# exp-4_sche.net
KiCad netlist of a schematic drawn in EAGLE
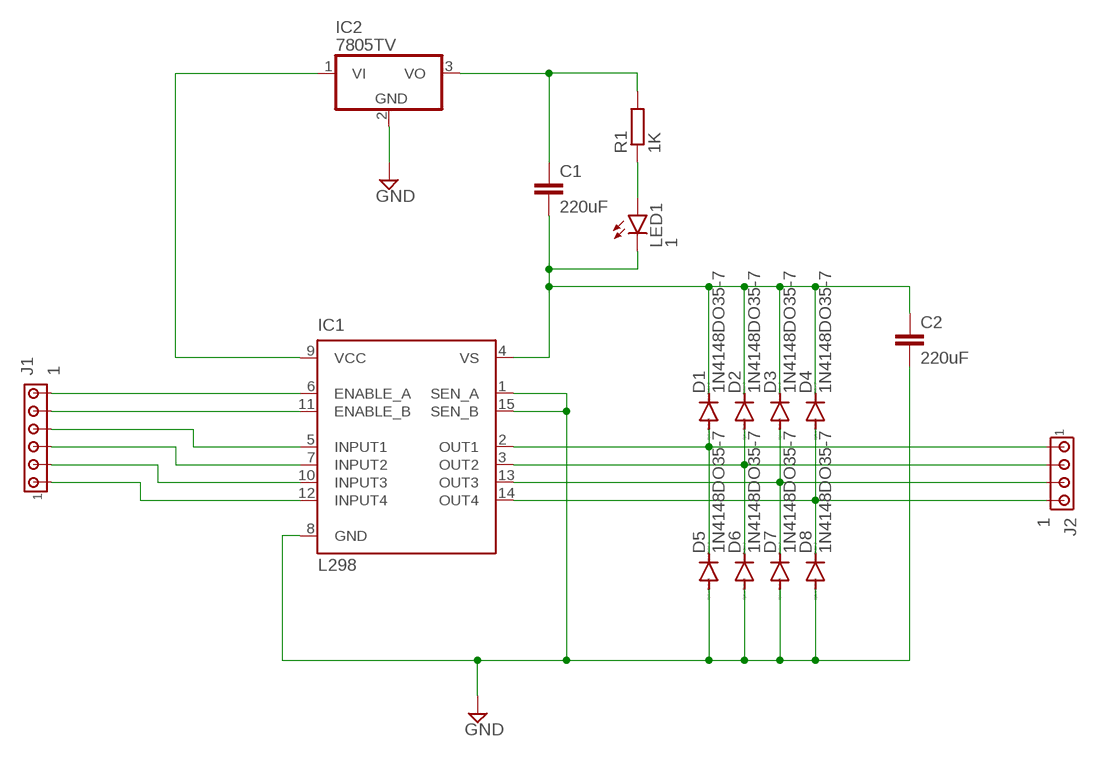
[diagram p0: schematic, sheet 1]

(export (version "E")
  (design (tool "Eeschema 10.0.6"))
  (components
    (comp (ref "C1")
      (value "220uF")
      (footprint "eagle-import:C2.5-3")
      (libsource (lib "eagle-import") (part "C2,5-3"))
    )
    (comp (ref "C2")
      (value "220uF")
      (footprint "eagle-import:C2.5-3")
      (libsource (lib "eagle-import") (part "C2,5-3"))
    )
    (comp (ref "D1")
      (value "1N4148DO35-7")
      (footprint "eagle-import:DO35-7")
      (libsource (lib "eagle-import") (part "1N4148DO35-7"))
    )
    (comp (ref "D2")
      (value "1N4148DO35-7")
      (footprint "eagle-import:DO35-7")
      (libsource (lib "eagle-import") (part "1N4148DO35-7"))
    )
    (comp (ref "D3")
      (value "1N4148DO35-7")
      (footprint "eagle-import:DO35-7")
      (libsource (lib "eagle-import") (part "1N4148DO35-7"))
    )
    (comp (ref "D4")
      (value "1N4148DO35-7")
      (footprint "eagle-import:DO35-7")
      (libsource (lib "eagle-import") (part "1N4148DO35-7"))
    )
    (comp (ref "D5")
      (value "1N4148DO35-7")
      (footprint "eagle-import:DO35-7")
      (libsource (lib "eagle-import") (part "1N4148DO35-7"))
    )
    (comp (ref "D6")
      (value "1N4148DO35-7")
      (footprint "eagle-import:DO35-7")
      (libsource (lib "eagle-import") (part "1N4148DO35-7"))
    )
    (comp (ref "D7")
      (value "1N4148DO35-7")
      (footprint "eagle-import:DO35-7")
      (libsource (lib "eagle-import") (part "1N4148DO35-7"))
    )
    (comp (ref "D8")
      (value "1N4148DO35-7")
      (footprint "eagle-import:DO35-7")
      (libsource (lib "eagle-import") (part "1N4148DO35-7"))
    )
    (comp (ref "IC1")
      (value "L298")
      (footprint "eagle-import:MULTIWATT-15")
      (fields (field (name "MPN") "L298N"))
      (libsource (lib "eagle-import") (part "L298"))
    )
    (comp (ref "IC2")
      (value "7805TV")
      (footprint "eagle-import:TO220V")
      (libsource (lib "eagle-import") (part "78TV05"))
    )
    (comp (ref "J1")
      (value "1")
      (footprint "eagle-import:1X6MTA")
      (libsource (lib "eagle-import") (part "MTA06-156"))
    )
    (comp (ref "J2")
      (value "1")
      (footprint "eagle-import:1X4MTA")
      (libsource (lib "eagle-import") (part "MTA04-156"))
    )
    (comp (ref "LED1")
      (value "1")
      (footprint "eagle-import:LED5MM")
      (libsource (lib "eagle-import") (part "LED5MM"))
    )
    (comp (ref "R1")
      (value "1K")
      (footprint "eagle-import:0204_7")
      (libsource (lib "eagle-import") (part "R-EU_0204/7"))
    )
  )
  (nets
    (net (code "1") (name "GND") (class "Default")
      (node (ref "C2") (pin "2") (pinfunction "2_2") (pintype "passive"))
      (node (ref "D5") (pin "A") (pinfunction "A_A") (pintype "passive"))
      (node (ref "D6") (pin "A") (pinfunction "A_A") (pintype "passive"))
      (node (ref "D7") (pin "A") (pinfunction "A_A") (pintype "passive"))
      (node (ref "D8") (pin "A") (pinfunction "A_A") (pintype "passive"))
      (node (ref "IC1") (pin "1") (pinfunction "SEN_A_1") (pintype "input"))
      (node (ref "IC1") (pin "15") (pinfunction "SEN_B_15") (pintype "input"))
      (node (ref "IC1") (pin "8") (pinfunction "GND_8") (pintype "power_in"))
      (node (ref "IC2") (pin "2") (pinfunction "GND_2") (pintype "passive"))
    )
    (net (code "2") (name "Net-(IC1-ENABLE_A)") (class "Default")
      (node (ref "IC1") (pin "6") (pinfunction "ENABLE_A_6") (pintype "input"))
      (node (ref "J1") (pin "6") (pinfunction "6_6") (pintype "passive"))
    )
    (net (code "3") (name "Net-(IC1-ENABLE_B)") (class "Default")
      (node (ref "IC1") (pin "11") (pinfunction "ENABLE_B_11") (pintype "input"))
      (node (ref "J1") (pin "5") (pinfunction "5_5") (pintype "passive"))
    )
    (net (code "4") (name "Net-(IC1-INPUT1)") (class "Default")
      (node (ref "IC1") (pin "5") (pinfunction "INPUT1_5") (pintype "input"))
      (node (ref "J1") (pin "4") (pinfunction "4_4") (pintype "passive"))
    )
    (net (code "5") (name "Net-(IC1-INPUT2)") (class "Default")
      (node (ref "IC1") (pin "7") (pinfunction "INPUT2_7") (pintype "input"))
      (node (ref "J1") (pin "3") (pinfunction "3_3") (pintype "passive"))
    )
    (net (code "6") (name "Net-(IC1-INPUT3)") (class "Default")
      (node (ref "IC1") (pin "10") (pinfunction "INPUT3_10") (pintype "input"))
      (node (ref "J1") (pin "2") (pinfunction "2_2") (pintype "passive"))
    )
    (net (code "7") (name "Net-(IC1-INPUT4)") (class "Default")
      (node (ref "IC1") (pin "12") (pinfunction "INPUT4_12") (pintype "input"))
      (node (ref "J1") (pin "1") (pinfunction "1_1") (pintype "passive"))
    )
    (net (code "8") (name "Net-(IC1-OUT1)") (class "Default")
      (node (ref "D1") (pin "A") (pinfunction "A_A") (pintype "passive"))
      (node (ref "D5") (pin "C") (pinfunction "C_C") (pintype "passive"))
      (node (ref "IC1") (pin "2") (pinfunction "OUT1_2") (pintype "output"))
      (node (ref "J2") (pin "1") (pinfunction "1_1") (pintype "passive"))
    )
    (net (code "9") (name "Net-(IC1-OUT2)") (class "Default")
      (node (ref "D2") (pin "A") (pinfunction "A_A") (pintype "passive"))
      (node (ref "D6") (pin "C") (pinfunction "C_C") (pintype "passive"))
      (node (ref "IC1") (pin "3") (pinfunction "OUT2_3") (pintype "output"))
      (node (ref "J2") (pin "2") (pinfunction "2_2") (pintype "passive"))
    )
    (net (code "10") (name "Net-(IC1-OUT3)") (class "Default")
      (node (ref "D3") (pin "A") (pinfunction "A_A") (pintype "passive"))
      (node (ref "D7") (pin "C") (pinfunction "C_C") (pintype "passive"))
      (node (ref "IC1") (pin "13") (pinfunction "OUT3_13") (pintype "output"))
      (node (ref "J2") (pin "3") (pinfunction "3_3") (pintype "passive"))
    )
    (net (code "11") (name "Net-(IC1-OUT4)") (class "Default")
      (node (ref "D4") (pin "A") (pinfunction "A_A") (pintype "passive"))
      (node (ref "D8") (pin "C") (pinfunction "C_C") (pintype "passive"))
      (node (ref "IC1") (pin "14") (pinfunction "OUT4_14") (pintype "output"))
      (node (ref "J2") (pin "4") (pinfunction "4_4") (pintype "passive"))
    )
    (net (code "12") (name "Net-(IC1-VCC)") (class "Default")
      (node (ref "IC1") (pin "9") (pinfunction "VCC_9") (pintype "power_in"))
      (node (ref "IC2") (pin "1") (pinfunction "VI_1") (pintype "input"))
    )
    (net (code "13") (name "Net-(IC1-VS)") (class "Default")
      (node (ref "C1") (pin "2") (pinfunction "2_2") (pintype "passive"))
      (node (ref "C2") (pin "1") (pinfunction "1_1") (pintype "passive"))
      (node (ref "D1") (pin "C") (pinfunction "C_C") (pintype "passive"))
      (node (ref "D2") (pin "C") (pinfunction "C_C") (pintype "passive"))
      (node (ref "D3") (pin "C") (pinfunction "C_C") (pintype "passive"))
      (node (ref "D4") (pin "C") (pinfunction "C_C") (pintype "passive"))
      (node (ref "IC1") (pin "4") (pinfunction "VS_4") (pintype "power_in"))
      (node (ref "LED1") (pin "K") (pinfunction "C_K") (pintype "passive"))
    )
    (net (code "14") (name "Net-(IC2-VO)") (class "Default")
      (node (ref "C1") (pin "1") (pinfunction "1_1") (pintype "passive"))
      (node (ref "IC2") (pin "3") (pinfunction "VO_3") (pintype "passive"))
      (node (ref "R1") (pin "2") (pinfunction "2_2") (pintype "passive"))
    )
    (net (code "15") (name "Net-(LED1-PadA)") (class "Default")
      (node (ref "LED1") (pin "A") (pinfunction "A_A") (pintype "passive"))
      (node (ref "R1") (pin "1") (pinfunction "1_1") (pintype "passive"))
    )
  )
)
